# Mini_project.net
KiCad netlist of a schematic drawn in Altium Designer
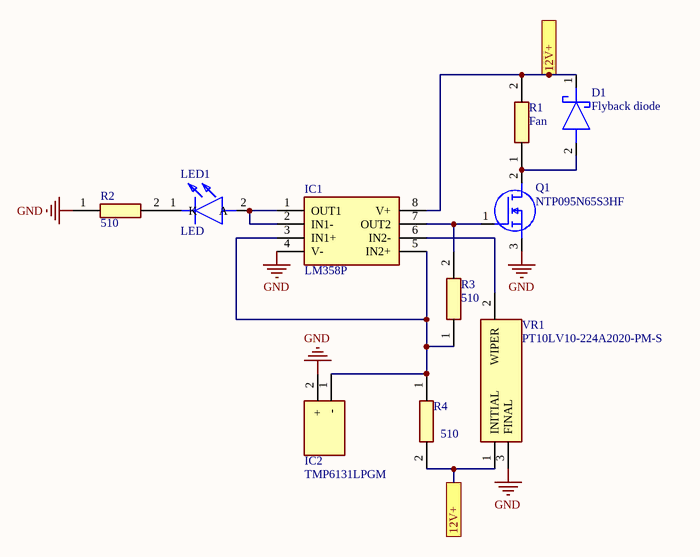
[diagram p0: Mini_project.SchDoc]

(export (version "E")
  (design (tool "Eeschema 10.0.6"))
  (components
    (comp (ref "D1")
      (value "Flyback diode")
      (footprint "DIOAD950W60L350D150")
      (description "SD101A-TR")
      (libsource (lib "SamacSys") (part "SD101A-TR"))
    )
    (comp (ref "IC1")
      (value "LM358P")
      (footprint "DIP794W53P254L959H508Q8N")
      (description "Integrated Circuit")
      (fields (field (name "MOUSER2 PART NUMBER") "595-LM358P"))
      (libsource (lib "SamacSys") (part "LM358P"))
    )
    (comp (ref "IC2")
      (value "TMP6131LPGM")
      (footprint "LMT01QLPGQ1")
      (description "Integrated Circuit")
      (libsource (lib "SamacSys") (part "TMP6131LPGM"))
    )
    (comp (ref "LED1")
      (value "LED")
      (footprint "C543AWMNCCCKK141")
      (description "C543A-WMN-CCCKK141")
      (fields (field (name "MOUSER2 PART NUMBER") "941-C543AWMNCCCKK141"))
      (libsource (lib "SamacSys") (part "C543A-WMN-CCCKK141"))
    )
    (comp (ref "Q1")
      (value "NTP095N65S3HF")
      (footprint "TO254P470X1016X2019-3P")
      (description "MOSFET (N-Channel)")
      (fields (field (name "MOUSER2 PART NUMBER") "863-NTP095N65S3HF"))
      (libsource (lib "SamacSys") (part "NTP095N65S3HF"))
    )
    (comp (ref "R1")
      (value "Fan")
      (footprint "RESAD3750W83L1670D520")
      (description "PR03000205100JAC00")
      (libsource (lib "") (part "PR03000205100JAC00_2"))
    )
    (comp (ref "R2")
      (value "510")
      (footprint "RESAD3750W83L1670D520")
      (description "PR03000205100JAC00")
      (libsource (lib "SamacSys") (part "PR03000205100JAC00"))
    )
    (comp (ref "R3")
      (value "510")
      (footprint "RESAD3750W83L1670D520")
      (description "PR03000205100JAC00")
      (libsource (lib "") (part "PR03000205100JAC00_2"))
    )
    (comp (ref "R4")
      (value "510")
      (footprint "RESAD3750W83L1670D520")
      (description "PR03000205100JAC00")
      (libsource (lib "") (part "PR03000205100JAC00_1"))
    )
    (comp (ref "VR1")
      (value "PT10LV10-224A2020-PM-S")
      (footprint "PT10LV10224A2020PMS")
      (description "Variable Resistor")
      (fields (field (name "MOUSER2 PART NUMBER") "531-PT1LV1224A22PMS"))
      (libsource (lib "SamacSys") (part "PT10LV10-224A2020-PM-S"))
    )
  )
  (nets
    (net (code "1") (name "/12V+") (class "Default")
      (node (ref "D1") (pin "1") (pinfunction "K_1") (pintype "passive"))
      (node (ref "IC1") (pin "8") (pinfunction "V+_8") (pintype "passive"))
      (node (ref "R1") (pin "2") (pinfunction "2_2") (pintype "passive"))
      (node (ref "R4") (pin "2") (pinfunction "2_2") (pintype "passive"))
      (node (ref "VR1") (pin "1") (pinfunction "INITIAL_1") (pintype "passive"))
    )
    (net (code "2") (name "GND") (class "Default")
      (node (ref "IC1") (pin "4") (pinfunction "V-_4") (pintype "passive"))
      (node (ref "IC2") (pin "2") (pinfunction "+_2") (pintype "passive"))
      (node (ref "Q1") (pin "3") (pinfunction "S_3") (pintype "passive"))
      (node (ref "R2") (pin "1") (pinfunction "1_1") (pintype "passive"))
      (node (ref "VR1") (pin "3") (pinfunction "FINAL_3") (pintype "passive"))
    )
    (net (code "3") (name "Net-(D1-A)") (class "Default")
      (node (ref "D1") (pin "2") (pinfunction "A_2") (pintype "passive"))
      (node (ref "Q1") (pin "2") (pinfunction "D_2") (pintype "passive"))
      (node (ref "R1") (pin "1") (pinfunction "1_1") (pintype "passive"))
    )
    (net (code "4") (name "Net-(IC1-IN1+)") (class "Default")
      (node (ref "IC1") (pin "3") (pinfunction "IN1+_3") (pintype "passive"))
      (node (ref "IC1") (pin "5") (pinfunction "IN2+_5") (pintype "passive"))
      (node (ref "IC2") (pin "1") (pinfunction "-_1") (pintype "passive"))
      (node (ref "R3") (pin "1") (pinfunction "1_1") (pintype "passive"))
      (node (ref "R4") (pin "1") (pinfunction "1_1") (pintype "passive"))
    )
    (net (code "5") (name "Net-(IC1-IN1-)") (class "Default")
      (node (ref "IC1") (pin "1") (pinfunction "OUT1_1") (pintype "passive"))
      (node (ref "IC1") (pin "2") (pinfunction "IN1-_2") (pintype "passive"))
      (node (ref "LED1") (pin "2") (pinfunction "A_2") (pintype "passive"))
    )
    (net (code "6") (name "Net-(IC1-IN2-)") (class "Default")
      (node (ref "IC1") (pin "6") (pinfunction "IN2-_6") (pintype "passive"))
      (node (ref "VR1") (pin "2") (pinfunction "WIPER_2") (pintype "passive"))
    )
    (net (code "7") (name "Net-(IC1-OUT2)") (class "Default")
      (node (ref "IC1") (pin "7") (pinfunction "OUT2_7") (pintype "passive"))
      (node (ref "Q1") (pin "1") (pinfunction "G_1") (pintype "passive"))
      (node (ref "R3") (pin "2") (pinfunction "2_2") (pintype "passive"))
    )
    (net (code "8") (name "Net-(LED1-K)") (class "Default")
      (node (ref "LED1") (pin "1") (pinfunction "K_1") (pintype "passive"))
      (node (ref "R2") (pin "2") (pinfunction "2_2") (pintype "passive"))
    )
  )
)
